# Bridge.net
KiCad netlist of a schematic drawn in Altium Designer
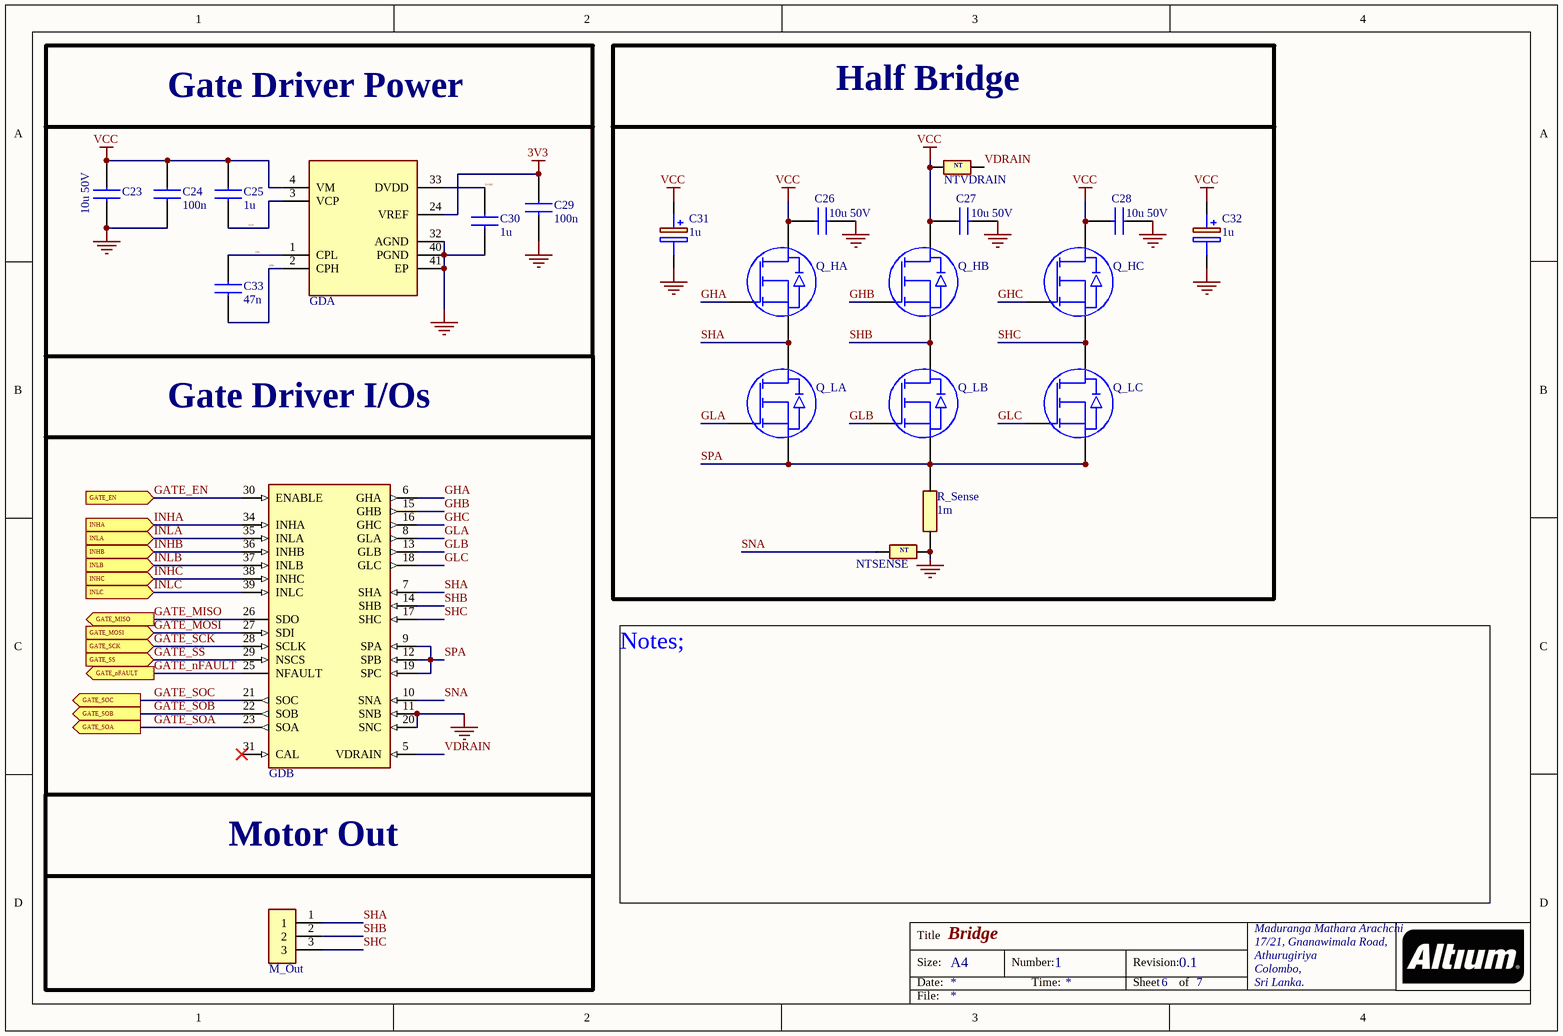
[diagram p0: Bridge.SchDoc]

(export (version "E")
  (design (tool "Eeschema 10.0.6"))
  (components
    (comp (ref "C23")
      (value "10u 50V")
      (footprint "RC_Car:CAPC1608X90N")
      (description "Capacitor")
      (fields
        (field (name "MANUFACTURER_PART_NUMBER") "GRM188R61H225KE11D")
        (field (name "MOUSER PART NUMBER") "81-GRM188R61H225KE1D")
      )
      (libsource (lib "RC_Car") (part "GRM188R61H225KE11D"))
    )
    (comp (ref "C24")
      (value "100n")
      (footprint "RC_Car:GRM18x")
      (description "Capacitor")
      (fields
        (field (name "MANUFACTURER_PART_NUMBER") "GRM188R72A104KA35D")
        (field (name "MOUSER PART NUMBER") "81-GRM188R72A104KA35")
      )
      (libsource (lib "RC_Car") (part "GRM188R72A104KA35D"))
    )
    (comp (ref "C25")
      (value "1u")
      (footprint "RC_Car:CAPC1608X90N")
      (description "Capacitor")
      (fields
        (field (name "MANUFACTURER_PART_NUMBER") "MSASU168SB5105KTNA01")
        (field (name "MOUSER PART NUMBER") "963-MSASU168SB5105KT")
      )
      (libsource (lib "RC_Car") (part "MSASU168SB5105KTNA01"))
    )
    (comp (ref "C26")
      (value "10u 50V")
      (footprint "RC_Car:CAPC1608X90N")
      (description "Capacitor")
      (fields
        (field (name "MANUFACTURER_PART_NUMBER") "GRM188R61H225KE11D")
        (field (name "MOUSER PART NUMBER") "81-GRM188R61H225KE1D")
      )
      (libsource (lib "RC_Car") (part "GRM188R61H225KE11D"))
    )
    (comp (ref "C27")
      (value "10u 50V")
      (footprint "RC_Car:CAPC1608X90N")
      (description "Capacitor")
      (fields
        (field (name "MANUFACTURER_PART_NUMBER") "GRM188R61H225KE11D")
        (field (name "MOUSER PART NUMBER") "81-GRM188R61H225KE1D")
      )
      (libsource (lib "RC_Car") (part "GRM188R61H225KE11D"))
    )
    (comp (ref "C28")
      (value "10u 50V")
      (footprint "RC_Car:CAPC1608X90N")
      (description "Capacitor")
      (fields
        (field (name "MANUFACTURER_PART_NUMBER") "GRM188R61H225KE11D")
        (field (name "MOUSER PART NUMBER") "81-GRM188R61H225KE1D")
      )
      (libsource (lib "RC_Car") (part "GRM188R61H225KE11D"))
    )
    (comp (ref "C29")
      (value "100n")
      (footprint "RC_Car:GRM18x")
      (description "Capacitor")
      (fields
        (field (name "MANUFACTURER_PART_NUMBER") "GRM188R72A104KA35D")
        (field (name "MOUSER PART NUMBER") "81-GRM188R72A104KA35")
      )
      (libsource (lib "RC_Car") (part "GRM188R72A104KA35D"))
    )
    (comp (ref "C30")
      (value "1u")
      (footprint "RC_Car:CAPC1608X90N")
      (description "Capacitor")
      (fields
        (field (name "MANUFACTURER_PART_NUMBER") "MSASU168SB5105KTNA01")
        (field (name "MOUSER PART NUMBER") "963-MSASU168SB5105KT")
      )
      (libsource (lib "RC_Car") (part "MSASU168SB5105KTNA01"))
    )
    (comp (ref "C31")
      (value "1u")
      (footprint "RC_Car:CAPAE430X550N")
      (description "Capacitor Polarised")
      (fields
        (field (name "MANUFACTURER_PART_NUMBER") "865081740001")
        (field (name "MOUSER PART NUMBER") "710-865081740001")
      )
      (libsource (lib "RC_Car") (part "865081740001"))
    )
    (comp (ref "C32")
      (value "1u")
      (footprint "RC_Car:CAPAE430X550N")
      (description "Capacitor Polarised")
      (fields
        (field (name "MANUFACTURER_PART_NUMBER") "865081740001")
        (field (name "MOUSER PART NUMBER") "710-865081740001")
      )
      (libsource (lib "RC_Car") (part "865081740001"))
    )
    (comp (ref "C33")
      (value "47n")
      (footprint "RC_Car:CAPC1608X89N")
      (description "Capacitor")
      (fields
        (field (name "MANUFACTURER_PART_NUMBER") "KAM15AR71H473KM")
        (field (name "MOUSER PART NUMBER") "581-KAM15AR71H473KM")
      )
      (libsource (lib "RC_Car") (part "KAM15AR71H473KM"))
    )
    (comp (ref "GD")
      (value "DRV8323SRTAR")
      (footprint "RC_Car:QFN50P600X600X80-41N-D")
      (description "Integrated Circuit")
      (fields (field (name "MOUSER PART NUMBER") "595-DRV8323SRTAR"))
      (libsource (lib "RC_Car") (part "DRV8323SRTAR"))
    )
    (comp (ref "M_Out")
      (value "MR60-F.G.Y")
      (footprint "MR60-F.G.Y")
      (description "High Current Pluggable Cables Assemblies ROHS")
      (libsource (lib "RC_Car") (part "MR60-F.G.Y"))
    )
    (comp (ref "NTSENSE")
      (value "NetTie_SMD")
      (footprint "NetTie_SMD")
      (libsource (lib "RC_Car") (part "NetTie_SMD"))
    )
    (comp (ref "NTVDRAIN")
      (value "NetTie_SMD")
      (footprint "NetTie_SMD")
      (libsource (lib "RC_Car") (part "NetTie_SMD"))
    )
    (comp (ref "Q_HA")
      (value "NTMFS5C430NT1G")
      (footprint "RC_Car:NTMFS4C022N")
      (description "MOSFET (N-Channel)")
      (fields (field (name "MOUSER PART NUMBER") "863-NTMFS5C430NT1G"))
      (libsource (lib "RC_Car") (part "NTMFS5C430NT1G"))
    )
    (comp (ref "Q_HB")
      (value "NTMFS5C430NT1G")
      (footprint "RC_Car:NTMFS4C022N")
      (description "MOSFET (N-Channel)")
      (fields (field (name "MOUSER PART NUMBER") "863-NTMFS5C430NT1G"))
      (libsource (lib "RC_Car") (part "NTMFS5C430NT1G"))
    )
    (comp (ref "Q_HC")
      (value "NTMFS5C430NT1G")
      (footprint "RC_Car:NTMFS4C022N")
      (description "MOSFET (N-Channel)")
      (fields (field (name "MOUSER PART NUMBER") "863-NTMFS5C430NT1G"))
      (libsource (lib "RC_Car") (part "NTMFS5C430NT1G"))
    )
    (comp (ref "Q_LA")
      (value "NTMFS5C430NT1G")
      (footprint "RC_Car:NTMFS4C022N")
      (description "MOSFET (N-Channel)")
      (fields (field (name "MOUSER PART NUMBER") "863-NTMFS5C430NT1G"))
      (libsource (lib "RC_Car") (part "NTMFS5C430NT1G"))
    )
    (comp (ref "Q_LB")
      (value "NTMFS5C430NT1G")
      (footprint "RC_Car:NTMFS4C022N")
      (description "MOSFET (N-Channel)")
      (fields (field (name "MOUSER PART NUMBER") "863-NTMFS5C430NT1G"))
      (libsource (lib "RC_Car") (part "NTMFS5C430NT1G"))
    )
    (comp (ref "Q_LC")
      (value "NTMFS5C430NT1G")
      (footprint "RC_Car:NTMFS4C022N")
      (description "MOSFET (N-Channel)")
      (fields (field (name "MOUSER PART NUMBER") "863-NTMFS5C430NT1G"))
      (libsource (lib "RC_Car") (part "NTMFS5C430NT1G"))
    )
    (comp (ref "R_Sense")
      (value "1m")
      (footprint "RC_Car:WSLF12061L000FE6")
      (description "Resistor")
      (fields
        (field (name "MANUFACTURER_PART_NUMBER") "WSLF12061L000FE6")
        (field (name "MOUSER PART NUMBER") "71-WSLF12061L000FE6")
      )
      (libsource (lib "RC_Car") (part "WSLF12061L000FE6"))
    )
  )
  (nets
    (net (code "1") (name "/CPH") (class "Default")
      (node (ref "C33") (pin "1") (pinfunction "1_1") (pintype "passive"))
      (node (ref "GD") (pin "2") (pinfunction "CPH_2") (pintype "power_in"))
    )
    (net (code "2") (name "/CPL") (class "Default")
      (node (ref "C33") (pin "2") (pinfunction "2_2") (pintype "passive"))
      (node (ref "GD") (pin "1") (pinfunction "CPL_1") (pintype "power_in"))
    )
    (net (code "3") (name "/DVDD") (class "Default")
      (node (ref "C30") (pin "2") (pinfunction "2_2") (pintype "passive"))
      (node (ref "GD") (pin "33") (pinfunction "DVDD_33") (pintype "power_in"))
    )
    (net (code "4") (name "/GATE_EN") (class "Default")
      (node (ref "GD") (pin "30") (pinfunction "ENABLE_30") (pintype "input"))
    )
    (net (code "5") (name "/GATE_MISO") (class "Default")
      (node (ref "GD") (pin "26") (pinfunction "SDO_26") (pintype "passive"))
    )
    (net (code "6") (name "/GATE_MOSI") (class "Default")
      (node (ref "GD") (pin "27") (pinfunction "SDI_27") (pintype "input"))
    )
    (net (code "7") (name "/GATE_SCK") (class "Default")
      (node (ref "GD") (pin "28") (pinfunction "SCLK_28") (pintype "input"))
    )
    (net (code "8") (name "/GATE_SOA") (class "Default")
      (node (ref "GD") (pin "23") (pinfunction "SOA_23") (pintype "output"))
    )
    (net (code "9") (name "/GATE_SOB") (class "Default")
      (node (ref "GD") (pin "22") (pinfunction "SOB_22") (pintype "output"))
    )
    (net (code "10") (name "/GATE_SOC") (class "Default")
      (node (ref "GD") (pin "21") (pinfunction "SOC_21") (pintype "output"))
    )
    (net (code "11") (name "/GATE_SS") (class "Default")
      (node (ref "GD") (pin "29") (pinfunction "NSCS_29") (pintype "input"))
    )
    (net (code "12") (name "/GATE_nFAULT") (class "Default")
      (node (ref "GD") (pin "25") (pinfunction "NFAULT_25") (pintype "passive"))
    )
    (net (code "13") (name "/GHA") (class "Default")
      (node (ref "GD") (pin "6") (pinfunction "GHA_6") (pintype "output"))
      (node (ref "Q_HA") (pin "4") (pinfunction "Gate_4") (pintype "passive"))
    )
    (net (code "14") (name "/GHB") (class "Default")
      (node (ref "GD") (pin "15") (pinfunction "GHB_15") (pintype "output"))
      (node (ref "Q_HB") (pin "4") (pinfunction "Gate_4") (pintype "passive"))
    )
    (net (code "15") (name "/GHC") (class "Default")
      (node (ref "GD") (pin "16") (pinfunction "GHC_16") (pintype "output"))
      (node (ref "Q_HC") (pin "4") (pinfunction "Gate_4") (pintype "passive"))
    )
    (net (code "16") (name "/GLA") (class "Default")
      (node (ref "GD") (pin "8") (pinfunction "GLA_8") (pintype "output"))
      (node (ref "Q_LA") (pin "4") (pinfunction "Gate_4") (pintype "passive"))
    )
    (net (code "17") (name "/GLB") (class "Default")
      (node (ref "GD") (pin "13") (pinfunction "GLB_13") (pintype "output"))
      (node (ref "Q_LB") (pin "4") (pinfunction "Gate_4") (pintype "passive"))
    )
    (net (code "18") (name "/GLC") (class "Default")
      (node (ref "GD") (pin "18") (pinfunction "GLC_18") (pintype "output"))
      (node (ref "Q_LC") (pin "4") (pinfunction "Gate_4") (pintype "passive"))
    )
    (net (code "19") (name "/INHA") (class "Default")
      (node (ref "GD") (pin "34") (pinfunction "INHA_34") (pintype "input"))
    )
    (net (code "20") (name "/INHB") (class "Default")
      (node (ref "GD") (pin "36") (pinfunction "INHB_36") (pintype "input"))
    )
    (net (code "21") (name "/INHC") (class "Default")
      (node (ref "GD") (pin "38") (pinfunction "INHC_38") (pintype "input"))
    )
    (net (code "22") (name "/INLA") (class "Default")
      (node (ref "GD") (pin "35") (pinfunction "INLA_35") (pintype "input"))
    )
    (net (code "23") (name "/INLB") (class "Default")
      (node (ref "GD") (pin "37") (pinfunction "INLB_37") (pintype "input"))
    )
    (net (code "24") (name "/INLC") (class "Default")
      (node (ref "GD") (pin "39") (pinfunction "INLC_39") (pintype "input"))
    )
    (net (code "25") (name "/SHA") (class "Default")
      (node (ref "GD") (pin "7") (pinfunction "SHA_7") (pintype "input"))
      (node (ref "M_Out") (pin "1") (pinfunction "1_1") (pintype "passive"))
      (node (ref "Q_HA") (pin "1") (pinfunction "S_1") (pintype "passive"))
      (node (ref "Q_HA") (pin "2") (pinfunction "S_2") (pintype "passive"))
      (node (ref "Q_HA") (pin "3") (pinfunction "S_3") (pintype "passive"))
      (node (ref "Q_LA") (pin "5") (pinfunction "D_5") (pintype "passive"))
      (node (ref "Q_LA") (pin "6") (pinfunction "D_6") (pintype "passive"))
      (node (ref "Q_LA") (pin "7") (pinfunction "D_7") (pintype "passive"))
      (node (ref "Q_LA") (pin "8") (pinfunction "D_8") (pintype "passive"))
      (node (ref "Q_LA") (pin "9") (pinfunction "D_9") (pintype "passive"))
    )
    (net (code "26") (name "/SHB") (class "Default")
      (node (ref "GD") (pin "14") (pinfunction "SHB_14") (pintype "input"))
      (node (ref "M_Out") (pin "2") (pinfunction "2_2") (pintype "passive"))
      (node (ref "Q_HB") (pin "1") (pinfunction "S_1") (pintype "passive"))
      (node (ref "Q_HB") (pin "2") (pinfunction "S_2") (pintype "passive"))
      (node (ref "Q_HB") (pin "3") (pinfunction "S_3") (pintype "passive"))
      (node (ref "Q_LB") (pin "5") (pinfunction "D_5") (pintype "passive"))
      (node (ref "Q_LB") (pin "6") (pinfunction "D_6") (pintype "passive"))
      (node (ref "Q_LB") (pin "7") (pinfunction "D_7") (pintype "passive"))
      (node (ref "Q_LB") (pin "8") (pinfunction "D_8") (pintype "passive"))
      (node (ref "Q_LB") (pin "9") (pinfunction "D_9") (pintype "passive"))
    )
    (net (code "27") (name "/SHC") (class "Default")
      (node (ref "GD") (pin "17") (pinfunction "SHC_17") (pintype "input"))
      (node (ref "M_Out") (pin "3") (pinfunction "3_3") (pintype "passive"))
      (node (ref "Q_HC") (pin "1") (pinfunction "S_1") (pintype "passive"))
      (node (ref "Q_HC") (pin "2") (pinfunction "S_2") (pintype "passive"))
      (node (ref "Q_HC") (pin "3") (pinfunction "S_3") (pintype "passive"))
      (node (ref "Q_LC") (pin "5") (pinfunction "D_5") (pintype "passive"))
      (node (ref "Q_LC") (pin "6") (pinfunction "D_6") (pintype "passive"))
      (node (ref "Q_LC") (pin "7") (pinfunction "D_7") (pintype "passive"))
      (node (ref "Q_LC") (pin "8") (pinfunction "D_8") (pintype "passive"))
      (node (ref "Q_LC") (pin "9") (pinfunction "D_9") (pintype "passive"))
    )
    (net (code "28") (name "/SNA") (class "Default")
      (node (ref "GD") (pin "10") (pinfunction "SNA_10") (pintype "input"))
      (node (ref "NTSENSE") (pin "1") (pinfunction "1_1") (pintype "passive"))
    )
    (net (code "29") (name "/SPA") (class "Default")
      (node (ref "GD") (pin "12") (pinfunction "SPB_12") (pintype "input"))
      (node (ref "GD") (pin "19") (pinfunction "SPC_19") (pintype "input"))
      (node (ref "GD") (pin "9") (pinfunction "SPA_9") (pintype "input"))
      (node (ref "Q_LA") (pin "1") (pinfunction "S_1") (pintype "passive"))
      (node (ref "Q_LA") (pin "2") (pinfunction "S_2") (pintype "passive"))
      (node (ref "Q_LA") (pin "3") (pinfunction "S_3") (pintype "passive"))
      (node (ref "Q_LB") (pin "1") (pinfunction "S_1") (pintype "passive"))
      (node (ref "Q_LB") (pin "2") (pinfunction "S_2") (pintype "passive"))
      (node (ref "Q_LB") (pin "3") (pinfunction "S_3") (pintype "passive"))
      (node (ref "Q_LC") (pin "1") (pinfunction "S_1") (pintype "passive"))
      (node (ref "Q_LC") (pin "2") (pinfunction "S_2") (pintype "passive"))
      (node (ref "Q_LC") (pin "3") (pinfunction "S_3") (pintype "passive"))
      (node (ref "R_Sense") (pin "2") (pinfunction "2_2") (pintype "passive"))
    )
    (net (code "30") (name "/VCP") (class "Default")
      (node (ref "C25") (pin "1") (pinfunction "1_1") (pintype "passive"))
      (node (ref "GD") (pin "3") (pinfunction "VCP_3") (pintype "power_in"))
    )
    (net (code "31") (name "/VDRAIN") (class "Default")
      (node (ref "GD") (pin "5") (pinfunction "VDRAIN_5") (pintype "input"))
      (node (ref "NTVDRAIN") (pin "2") (pinfunction "2_2") (pintype "passive"))
    )
    (net (code "32") (name "3V3") (class "Default")
      (node (ref "C29") (pin "2") (pinfunction "2_2") (pintype "passive"))
      (node (ref "GD") (pin "24") (pinfunction "VREF_24") (pintype "power_in"))
    )
    (net (code "33") (name "GND") (class "Default")
      (node (ref "C23") (pin "1") (pinfunction "1_1") (pintype "passive"))
      (node (ref "C24") (pin "1") (pinfunction "1_1") (pintype "passive"))
      (node (ref "C26") (pin "2") (pinfunction "2_2") (pintype "passive"))
      (node (ref "C27") (pin "2") (pinfunction "2_2") (pintype "passive"))
      (node (ref "C28") (pin "2") (pinfunction "2_2") (pintype "passive"))
      (node (ref "C29") (pin "1") (pinfunction "1_1") (pintype "passive"))
      (node (ref "C30") (pin "1") (pinfunction "1_1") (pintype "passive"))
      (node (ref "C31") (pin "2") (pinfunction "-_2") (pintype "passive"))
      (node (ref "C32") (pin "2") (pinfunction "-_2") (pintype "passive"))
      (node (ref "GD") (pin "11") (pinfunction "SNB_11") (pintype "input"))
      (node (ref "GD") (pin "20") (pinfunction "SNC_20") (pintype "input"))
      (node (ref "GD") (pin "32") (pinfunction "AGND_32") (pintype "power_in"))
      (node (ref "GD") (pin "40") (pinfunction "PGND_40") (pintype "power_in"))
      (node (ref "GD") (pin "41") (pinfunction "EP_41") (pintype "power_in"))
      (node (ref "NTSENSE") (pin "2") (pinfunction "2_2") (pintype "passive"))
      (node (ref "R_Sense") (pin "1") (pinfunction "1_1") (pintype "passive"))
    )
    (net (code "34") (name "VCC") (class "Default")
      (node (ref "C23") (pin "2") (pinfunction "2_2") (pintype "passive"))
      (node (ref "C24") (pin "2") (pinfunction "2_2") (pintype "passive"))
      (node (ref "C25") (pin "2") (pinfunction "2_2") (pintype "passive"))
      (node (ref "C26") (pin "1") (pinfunction "1_1") (pintype "passive"))
      (node (ref "C27") (pin "1") (pinfunction "1_1") (pintype "passive"))
      (node (ref "C28") (pin "1") (pinfunction "1_1") (pintype "passive"))
      (node (ref "C31") (pin "1") (pinfunction "+_1") (pintype "passive"))
      (node (ref "C32") (pin "1") (pinfunction "+_1") (pintype "passive"))
      (node (ref "GD") (pin "4") (pinfunction "VM_4") (pintype "power_in"))
      (node (ref "NTVDRAIN") (pin "1") (pinfunction "1_1") (pintype "passive"))
      (node (ref "Q_HA") (pin "5") (pinfunction "D_5") (pintype "passive"))
      (node (ref "Q_HA") (pin "6") (pinfunction "D_6") (pintype "passive"))
      (node (ref "Q_HA") (pin "7") (pinfunction "D_7") (pintype "passive"))
      (node (ref "Q_HA") (pin "8") (pinfunction "D_8") (pintype "passive"))
      (node (ref "Q_HA") (pin "9") (pinfunction "D_9") (pintype "passive"))
      (node (ref "Q_HB") (pin "5") (pinfunction "D_5") (pintype "passive"))
      (node (ref "Q_HB") (pin "6") (pinfunction "D_6") (pintype "passive"))
      (node (ref "Q_HB") (pin "7") (pinfunction "D_7") (pintype "passive"))
      (node (ref "Q_HB") (pin "8") (pinfunction "D_8") (pintype "passive"))
      (node (ref "Q_HB") (pin "9") (pinfunction "D_9") (pintype "passive"))
      (node (ref "Q_HC") (pin "5") (pinfunction "D_5") (pintype "passive"))
      (node (ref "Q_HC") (pin "6") (pinfunction "D_6") (pintype "passive"))
      (node (ref "Q_HC") (pin "7") (pinfunction "D_7") (pintype "passive"))
      (node (ref "Q_HC") (pin "8") (pinfunction "D_8") (pintype "passive"))
      (node (ref "Q_HC") (pin "9") (pinfunction "D_9") (pintype "passive"))
    )
    (net (code "35") (name "unconnected-(GDB-CAL-Pad31)") (class "Default")
      (node (ref "GD") (pin "31") (pinfunction "CAL_31") (pintype "input+no_connect"))
    )
  )
)
